# controle_moteur_fat_bjt.net
KiCad netlist of a schematic drawn in EAGLE
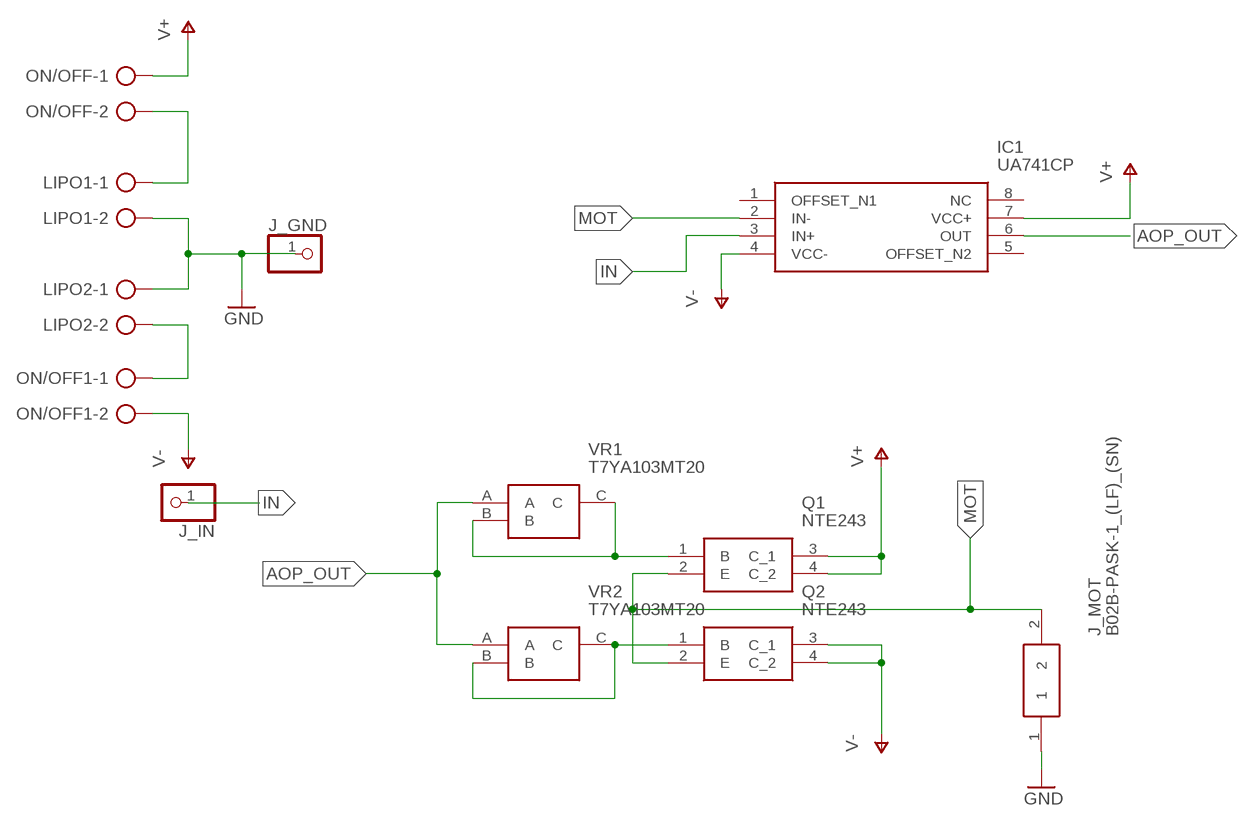
[diagram p0: schematic, sheet 1]

(export (version "E")
  (design (tool "Eeschema 10.0.6"))
  (components
    (comp (ref "IC1")
      (value "UA741CP")
      (footprint "eagle-import:DIP794W53P254L959H508Q8N")
      (fields (field (name "MOUSER_PART_NUMBER") "595-UA741CP") (field (name "RS_PART_NUMBER") "0305311P"))
      (libsource (lib "eagle-import") (part "UA741CP"))
    )
    (comp (ref "J_GND")
      (value "PINHD-1X1")
      (footprint "eagle-import:1X01")
      (libsource (lib "eagle-import") (part "PINHD-1X1"))
    )
    (comp (ref "J_IN")
      (value "PINHD-1X1")
      (footprint "eagle-import:1X01")
      (libsource (lib "eagle-import") (part "PINHD-1X1"))
    )
    (comp (ref "J_MOT")
      (value "B02B-PASK-1_(LF)_(SN)")
      (footprint "eagle-import:B02BPASK1LFSN")
      (fields
        (field (name "MANUFACTURER_PART_NUMBER") "B02B-PASK-1 (LF) (SN)")
        (field (name "RS_PART_NUMBER") "5128585P")
      )
      (libsource (lib "eagle-import") (part "B02B-PASK-1_(LF)_(SN)"))
    )
    (comp (ref "LIPO1")
      (value "AK500/2")
      (footprint "eagle-import:AK500_2")
      (libsource (lib "eagle-import") (part "AK500/2"))
    )
    (comp (ref "LIPO2")
      (value "AK500/2")
      (footprint "eagle-import:AK500_2")
      (libsource (lib "eagle-import") (part "AK500/2"))
    )
    (comp (ref "ON/OFF")
      (value "AK500/2")
      (footprint "eagle-import:AK500_2")
      (libsource (lib "eagle-import") (part "AK500/2"))
    )
    (comp (ref "ON/OFF1")
      (value "AK500/2")
      (footprint "eagle-import:AK500_2")
      (libsource (lib "eagle-import") (part "AK500/2"))
    )
    (comp (ref "Q1")
      (value "NTE243")
      (footprint "eagle-import:NTE243")
      (libsource (lib "eagle-import") (part "NTE243"))
    )
    (comp (ref "Q2")
      (value "NTE243")
      (footprint "eagle-import:NTE243")
      (libsource (lib "eagle-import") (part "NTE243"))
    )
    (comp (ref "VR1")
      (value "T7YA103MT20")
      (footprint "eagle-import:T7YA")
      (fields (field (name "RS_PART_NUMBER") "3746787P"))
      (libsource (lib "eagle-import") (part "T7YA103MT20"))
    )
    (comp (ref "VR2")
      (value "T7YA103MT20")
      (footprint "eagle-import:T7YA")
      (fields (field (name "RS_PART_NUMBER") "3746787P"))
      (libsource (lib "eagle-import") (part "T7YA103MT20"))
    )
  )
  (nets
    (net (code "1") (name "AOP_OUT") (class "Default")
      (node (ref "IC1") (pin "6") (pinfunction "OUT_6") (pintype "output"))
      (node (ref "VR1") (pin "A") (pinfunction "A_A") (pintype "bidirectional"))
      (node (ref "VR2") (pin "A") (pinfunction "A_A") (pintype "bidirectional"))
    )
    (net (code "2") (name "GND") (class "Default")
      (node (ref "J_GND") (pin "1") (pinfunction "1_1") (pintype "passive"))
      (node (ref "J_MOT") (pin "1") (pinfunction "1_1") (pintype "bidirectional"))
      (node (ref "LIPO1") (pin "2") (pinfunction "KL_2") (pintype "passive"))
      (node (ref "LIPO2") (pin "1") (pinfunction "KL_1") (pintype "passive"))
    )
    (net (code "3") (name "IN") (class "Default")
      (node (ref "IC1") (pin "3") (pinfunction "IN+_3") (pintype "input"))
      (node (ref "J_IN") (pin "1") (pinfunction "1_1") (pintype "passive"))
    )
    (net (code "4") (name "MOT") (class "Default")
      (node (ref "IC1") (pin "2") (pinfunction "IN-_2") (pintype "input"))
      (node (ref "J_MOT") (pin "2") (pinfunction "2_2") (pintype "bidirectional"))
      (node (ref "Q1") (pin "2") (pinfunction "E_2") (pintype "bidirectional"))
      (node (ref "Q2") (pin "2") (pinfunction "E_2") (pintype "bidirectional"))
    )
    (net (code "5") (name "Net-(LIPO1A-KL)") (class "Default")
      (node (ref "LIPO1") (pin "1") (pinfunction "KL_1") (pintype "passive"))
      (node (ref "ON/OFF") (pin "2") (pinfunction "KL_2") (pintype "passive"))
    )
    (net (code "6") (name "Net-(LIPO2B-KL)") (class "Default")
      (node (ref "LIPO2") (pin "2") (pinfunction "KL_2") (pintype "passive"))
      (node (ref "ON/OFF1") (pin "1") (pinfunction "KL_1") (pintype "passive"))
    )
    (net (code "7") (name "Net-(Q1-B)") (class "Default")
      (node (ref "Q1") (pin "1") (pinfunction "B_1") (pintype "bidirectional"))
      (node (ref "VR1") (pin "B") (pinfunction "B_B") (pintype "bidirectional"))
      (node (ref "VR1") (pin "C") (pinfunction "C_C") (pintype "bidirectional"))
    )
    (net (code "8") (name "Net-(Q2-B)") (class "Default")
      (node (ref "Q2") (pin "1") (pinfunction "B_1") (pintype "bidirectional"))
      (node (ref "VR2") (pin "B") (pinfunction "B_B") (pintype "bidirectional"))
      (node (ref "VR2") (pin "C") (pinfunction "C_C") (pintype "bidirectional"))
    )
    (net (code "9") (name "V+") (class "Default")
      (node (ref "IC1") (pin "7") (pinfunction "VCC+_7") (pintype "power_in"))
      (node (ref "ON/OFF") (pin "1") (pinfunction "KL_1") (pintype "passive"))
      (node (ref "Q1") (pin "3") (pinfunction "C_1_3") (pintype "bidirectional"))
      (node (ref "Q1") (pin "4") (pinfunction "C_2_4") (pintype "bidirectional"))
    )
    (net (code "10") (name "V-") (class "Default")
      (node (ref "IC1") (pin "4") (pinfunction "VCC-_4") (pintype "power_in"))
      (node (ref "ON/OFF1") (pin "2") (pinfunction "KL_2") (pintype "passive"))
      (node (ref "Q2") (pin "3") (pinfunction "C_1_3") (pintype "bidirectional"))
      (node (ref "Q2") (pin "4") (pinfunction "C_2_4") (pintype "bidirectional"))
    )
    (net (code "11") (name "unconnected-(IC1-NC-Pad8)") (class "Default")
      (node (ref "IC1") (pin "8") (pinfunction "NC_8") (pintype "no_connect"))
    )
    (net (code "12") (name "unconnected-(IC1-OFFSET_N1-Pad1)") (class "Default")
      (node (ref "IC1") (pin "1") (pinfunction "OFFSET_N1_1") (pintype "bidirectional"))
    )
    (net (code "13") (name "unconnected-(IC1-OFFSET_N2-Pad5)") (class "Default")
      (node (ref "IC1") (pin "5") (pinfunction "OFFSET_N2_5") (pintype "bidirectional"))
    )
  )
)
